# currentU_conditioning.net
KiCad netlist of a schematic drawn in Altium Designer
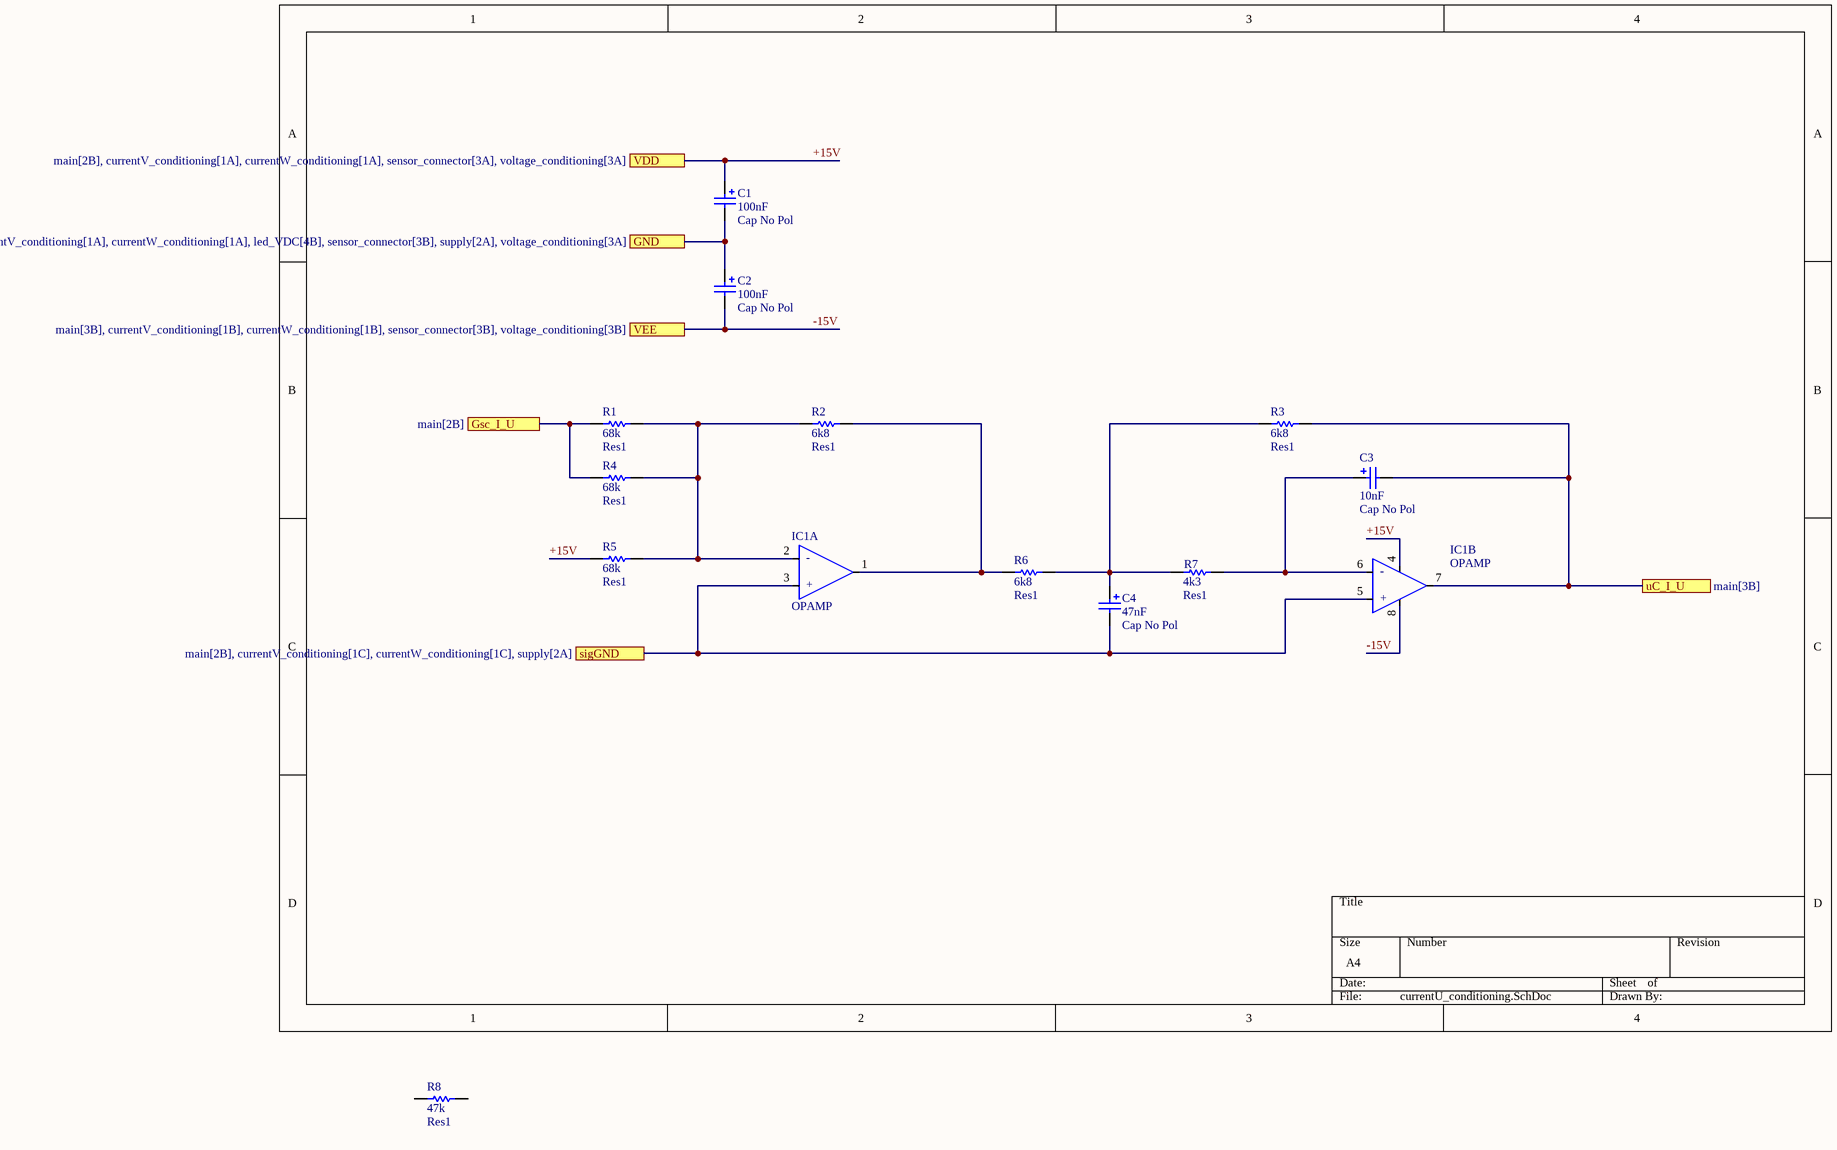
[diagram p0: currentU_conditioning.SchDoc]

(export (version "E")
  (design (tool "Eeschema 10.0.6"))
  (components
    (comp (ref "C1")
      (value "Cap No Pol")
      (footprint "RAD-0.1")
      (description "Polarized Capacitor (Radial)")
      (fields (field (name "ALTIUM_VALUE") "100nF") (field (name "PUBLISHER") "Altium Limited"))
      (libsource (lib "LABSTEPS_Project") (part "Cap No Pol"))
    )
    (comp (ref "C2")
      (value "Cap No Pol")
      (footprint "RAD-0.1")
      (description "Polarized Capacitor (Radial)")
      (fields (field (name "ALTIUM_VALUE") "100nF") (field (name "PUBLISHER") "Altium Limited"))
      (libsource (lib "LABSTEPS_Project") (part "Cap No Pol"))
    )
    (comp (ref "C3")
      (value "Cap No Pol")
      (footprint "RAD-0.1")
      (description "Polarized Capacitor (Radial)")
      (fields (field (name "ALTIUM_VALUE") "10nF") (field (name "PUBLISHER") "Altium Limited"))
      (libsource (lib "LABSTEPS_Project") (part "Cap No Pol"))
    )
    (comp (ref "C4")
      (value "Cap No Pol")
      (footprint "RAD-0.1")
      (description "Polarized Capacitor (Radial)")
      (fields (field (name "ALTIUM_VALUE") "47nF") (field (name "PUBLISHER") "Altium Limited"))
      (libsource (lib "LABSTEPS_Project") (part "Cap No Pol"))
    )
    (comp (ref "IC1")
      (value "OPAMP")
      (footprint "DIP-8")
      (description "ADTL082")
      (libsource (lib "LABSTEPS_Project") (part "ADTL082"))
    )
    (comp (ref "R1")
      (value "Res1")
      (footprint "AXIAL-0.3")
      (description "Resistor")
      (fields (field (name "ALTIUM_VALUE") "68k") (field (name "PUBLISHER") "Altium Limited"))
      (libsource (lib "LABSTEPS_Project") (part "Res1"))
    )
    (comp (ref "R2")
      (value "Res1")
      (footprint "AXIAL-0.3")
      (description "Resistor")
      (fields (field (name "ALTIUM_VALUE") "6k8") (field (name "PUBLISHER") "Altium Limited"))
      (libsource (lib "LABSTEPS_Project") (part "Res1"))
    )
    (comp (ref "R3")
      (value "Res1")
      (footprint "AXIAL-0.3")
      (description "Resistor")
      (fields (field (name "ALTIUM_VALUE") "6k8") (field (name "PUBLISHER") "Altium Limited"))
      (libsource (lib "LABSTEPS_Project") (part "Res1"))
    )
    (comp (ref "R4")
      (value "Res1")
      (footprint "AXIAL-0.3")
      (description "Resistor")
      (fields (field (name "ALTIUM_VALUE") "68k") (field (name "PUBLISHER") "Altium Limited"))
      (libsource (lib "LABSTEPS_Project") (part "Res1"))
    )
    (comp (ref "R5")
      (value "Res1")
      (footprint "AXIAL-0.3")
      (description "Resistor")
      (fields (field (name "ALTIUM_VALUE") "68k") (field (name "PUBLISHER") "Altium Limited"))
      (libsource (lib "LABSTEPS_Project") (part "Res1"))
    )
    (comp (ref "R6")
      (value "Res1")
      (footprint "AXIAL-0.3")
      (description "Resistor")
      (fields (field (name "ALTIUM_VALUE") "6k8") (field (name "PUBLISHER") "Altium Limited"))
      (libsource (lib "LABSTEPS_Project") (part "Res1"))
    )
    (comp (ref "R7")
      (value "Res1")
      (footprint "AXIAL-0.3")
      (description "Resistor")
      (fields (field (name "ALTIUM_VALUE") "4k3") (field (name "PUBLISHER") "Altium Limited"))
      (libsource (lib "LABSTEPS_Project") (part "Res1"))
    )
    (comp (ref "R8")
      (value "Res1")
      (footprint "AXIAL-0.3")
      (description "Resistor")
      (fields (field (name "ALTIUM_VALUE") "47k") (field (name "PUBLISHER") "Altium Limited"))
      (libsource (lib "LABSTEPS_Project") (part "Res1"))
    )
  )
  (nets
    (net (code "1") (name "/+15V") (class "Default")
      (node (ref "C1") (pin "1") (pinfunction "1_1") (pintype "passive"))
      (node (ref "IC1") (pin "4") (pinfunction "-V_4") (pintype "passive"))
      (node (ref "R5") (pin "1") (pinfunction "1_1") (pintype "passive"))
    )
    (net (code "2") (name "/-15V") (class "Default")
      (node (ref "C2") (pin "2") (pinfunction "2_2") (pintype "passive"))
      (node (ref "IC1") (pin "8") (pinfunction "V+_8") (pintype "passive"))
    )
    (net (code "3") (name "/GND") (class "Default")
      (node (ref "C1") (pin "2") (pinfunction "2_2") (pintype "passive"))
      (node (ref "C2") (pin "1") (pinfunction "1_1") (pintype "passive"))
    )
    (net (code "4") (name "/Gsc_I_U") (class "Default")
      (node (ref "R1") (pin "1") (pinfunction "1_1") (pintype "passive"))
      (node (ref "R4") (pin "1") (pinfunction "1_1") (pintype "passive"))
    )
    (net (code "5") (name "/sigGND") (class "Default")
      (node (ref "C4") (pin "2") (pinfunction "2_2") (pintype "passive"))
      (node (ref "IC1") (pin "3") (pinfunction "IN_A_+_3") (pintype "passive"))
      (node (ref "IC1") (pin "5") (pinfunction "IN_B_+_5") (pintype "passive"))
    )
    (net (code "6") (name "/uC_I_U") (class "Default")
      (node (ref "C3") (pin "2") (pinfunction "2_2") (pintype "passive"))
      (node (ref "IC1") (pin "7") (pinfunction "OUT_B_7") (pintype "passive"))
      (node (ref "R3") (pin "2") (pinfunction "2_2") (pintype "passive"))
    )
    (net (code "7") (name "Net-(C4-Pad1)") (class "Default")
      (node (ref "C4") (pin "1") (pinfunction "1_1") (pintype "passive"))
      (node (ref "R3") (pin "1") (pinfunction "1_1") (pintype "passive"))
      (node (ref "R6") (pin "2") (pinfunction "2_2") (pintype "passive"))
      (node (ref "R7") (pin "1") (pinfunction "1_1") (pintype "passive"))
    )
    (net (code "8") (name "Net-(IC1A-IN_A_-)") (class "Default")
      (node (ref "IC1") (pin "2") (pinfunction "IN_A_-_2") (pintype "passive"))
      (node (ref "R1") (pin "2") (pinfunction "2_2") (pintype "passive"))
      (node (ref "R2") (pin "1") (pinfunction "1_1") (pintype "passive"))
      (node (ref "R4") (pin "2") (pinfunction "2_2") (pintype "passive"))
      (node (ref "R5") (pin "2") (pinfunction "2_2") (pintype "passive"))
    )
    (net (code "9") (name "Net-(IC1A-OUT_A)") (class "Default")
      (node (ref "IC1") (pin "1") (pinfunction "OUT_A_1") (pintype "passive"))
      (node (ref "R2") (pin "2") (pinfunction "2_2") (pintype "passive"))
      (node (ref "R6") (pin "1") (pinfunction "1_1") (pintype "passive"))
    )
    (net (code "10") (name "Net-(IC1B-IN_B_-)") (class "Default")
      (node (ref "C3") (pin "1") (pinfunction "1_1") (pintype "passive"))
      (node (ref "IC1") (pin "6") (pinfunction "IN_B_-_6") (pintype "passive"))
      (node (ref "R7") (pin "2") (pinfunction "2_2") (pintype "passive"))
    )
    (net (code "11") (name "unconnected-(R8-Pad1)") (class "Default")
      (node (ref "R8") (pin "1") (pinfunction "1_1") (pintype "passive"))
    )
    (net (code "12") (name "unconnected-(R8-Pad2)") (class "Default")
      (node (ref "R8") (pin "2") (pinfunction "2_2") (pintype "passive"))
    )
  )
)
